# LED_POV_RGB.net
KiCad netlist of a schematic drawn in EAGLE
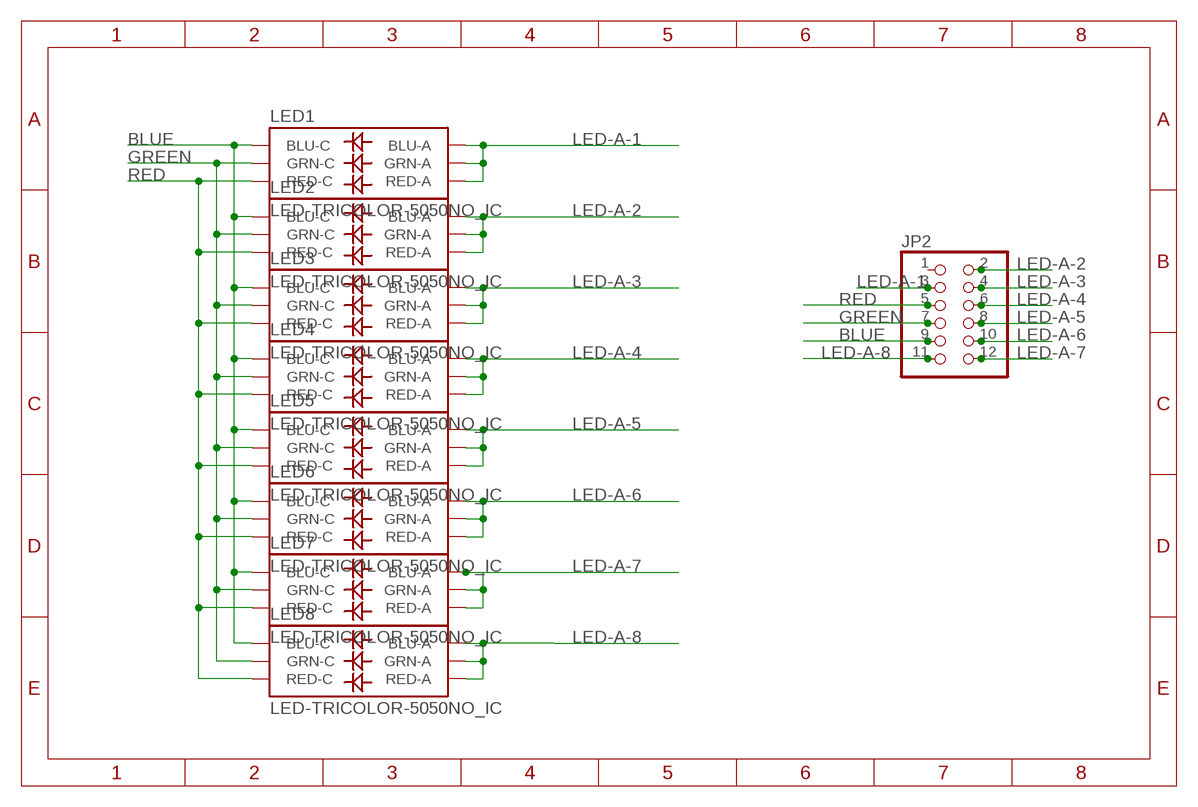
[diagram p0: schematic, sheet 1]

(export (version "E")
  (design (tool "Eeschema 10.0.6"))
  (components
    (comp (ref "JP2")
      (value "PINHD-2X6")
      (footprint "eagle-import:2X06")
      (libsource (lib "eagle-import") (part "PINHD-2X6"))
    )
    (comp (ref "LED1")
      (value "LED-TRICOLOR-5050NO_IC")
      (footprint "eagle-import:LED-TRICOLOR-5050")
      (libsource (lib "eagle-import") (part "LED-TRICOLOR-5050NO_IC"))
    )
    (comp (ref "LED2")
      (value "LED-TRICOLOR-5050NO_IC")
      (footprint "eagle-import:LED-TRICOLOR-5050")
      (libsource (lib "eagle-import") (part "LED-TRICOLOR-5050NO_IC"))
    )
    (comp (ref "LED3")
      (value "LED-TRICOLOR-5050NO_IC")
      (footprint "eagle-import:LED-TRICOLOR-5050")
      (libsource (lib "eagle-import") (part "LED-TRICOLOR-5050NO_IC"))
    )
    (comp (ref "LED4")
      (value "LED-TRICOLOR-5050NO_IC")
      (footprint "eagle-import:LED-TRICOLOR-5050")
      (libsource (lib "eagle-import") (part "LED-TRICOLOR-5050NO_IC"))
    )
    (comp (ref "LED5")
      (value "LED-TRICOLOR-5050NO_IC")
      (footprint "eagle-import:LED-TRICOLOR-5050")
      (libsource (lib "eagle-import") (part "LED-TRICOLOR-5050NO_IC"))
    )
    (comp (ref "LED6")
      (value "LED-TRICOLOR-5050NO_IC")
      (footprint "eagle-import:LED-TRICOLOR-5050")
      (libsource (lib "eagle-import") (part "LED-TRICOLOR-5050NO_IC"))
    )
    (comp (ref "LED7")
      (value "LED-TRICOLOR-5050NO_IC")
      (footprint "eagle-import:LED-TRICOLOR-5050")
      (libsource (lib "eagle-import") (part "LED-TRICOLOR-5050NO_IC"))
    )
    (comp (ref "LED8")
      (value "LED-TRICOLOR-5050NO_IC")
      (footprint "eagle-import:LED-TRICOLOR-5050")
      (libsource (lib "eagle-import") (part "LED-TRICOLOR-5050NO_IC"))
    )
  )
  (nets
    (net (code "1") (name "/BLUE") (class "Default")
      (node (ref "JP2") (pin "9") (pinfunction "9_9") (pintype "passive"))
      (node (ref "LED1") (pin "4") (pinfunction "BLU-C_4") (pintype "bidirectional"))
      (node (ref "LED2") (pin "4") (pinfunction "BLU-C_4") (pintype "bidirectional"))
      (node (ref "LED3") (pin "4") (pinfunction "BLU-C_4") (pintype "bidirectional"))
      (node (ref "LED4") (pin "4") (pinfunction "BLU-C_4") (pintype "bidirectional"))
      (node (ref "LED5") (pin "4") (pinfunction "BLU-C_4") (pintype "bidirectional"))
      (node (ref "LED6") (pin "4") (pinfunction "BLU-C_4") (pintype "bidirectional"))
      (node (ref "LED7") (pin "4") (pinfunction "BLU-C_4") (pintype "bidirectional"))
      (node (ref "LED8") (pin "4") (pinfunction "BLU-C_4") (pintype "bidirectional"))
    )
    (net (code "2") (name "/GREEN") (class "Default")
      (node (ref "JP2") (pin "7") (pinfunction "7_7") (pintype "passive"))
      (node (ref "LED1") (pin "6") (pinfunction "GRN-C_6") (pintype "bidirectional"))
      (node (ref "LED2") (pin "6") (pinfunction "GRN-C_6") (pintype "bidirectional"))
      (node (ref "LED3") (pin "6") (pinfunction "GRN-C_6") (pintype "bidirectional"))
      (node (ref "LED4") (pin "6") (pinfunction "GRN-C_6") (pintype "bidirectional"))
      (node (ref "LED5") (pin "6") (pinfunction "GRN-C_6") (pintype "bidirectional"))
      (node (ref "LED6") (pin "6") (pinfunction "GRN-C_6") (pintype "bidirectional"))
      (node (ref "LED7") (pin "6") (pinfunction "GRN-C_6") (pintype "bidirectional"))
      (node (ref "LED8") (pin "6") (pinfunction "GRN-C_6") (pintype "bidirectional"))
    )
    (net (code "3") (name "/LED-A-1") (class "Default")
      (node (ref "JP2") (pin "3") (pinfunction "3_3") (pintype "passive"))
      (node (ref "LED1") (pin "1") (pinfunction "GRN-A_1") (pintype "bidirectional"))
      (node (ref "LED1") (pin "2") (pinfunction "RED-A_2") (pintype "bidirectional"))
      (node (ref "LED1") (pin "3") (pinfunction "BLU-A_3") (pintype "bidirectional"))
    )
    (net (code "4") (name "/LED-A-2") (class "Default")
      (node (ref "JP2") (pin "2") (pinfunction "2_2") (pintype "passive"))
      (node (ref "LED2") (pin "1") (pinfunction "GRN-A_1") (pintype "bidirectional"))
      (node (ref "LED2") (pin "2") (pinfunction "RED-A_2") (pintype "bidirectional"))
      (node (ref "LED2") (pin "3") (pinfunction "BLU-A_3") (pintype "bidirectional"))
    )
    (net (code "5") (name "/LED-A-3") (class "Default")
      (node (ref "JP2") (pin "4") (pinfunction "4_4") (pintype "passive"))
      (node (ref "LED3") (pin "1") (pinfunction "GRN-A_1") (pintype "bidirectional"))
      (node (ref "LED3") (pin "2") (pinfunction "RED-A_2") (pintype "bidirectional"))
      (node (ref "LED3") (pin "3") (pinfunction "BLU-A_3") (pintype "bidirectional"))
    )
    (net (code "6") (name "/LED-A-4") (class "Default")
      (node (ref "JP2") (pin "6") (pinfunction "6_6") (pintype "passive"))
      (node (ref "LED4") (pin "1") (pinfunction "GRN-A_1") (pintype "bidirectional"))
      (node (ref "LED4") (pin "2") (pinfunction "RED-A_2") (pintype "bidirectional"))
      (node (ref "LED4") (pin "3") (pinfunction "BLU-A_3") (pintype "bidirectional"))
    )
    (net (code "7") (name "/LED-A-5") (class "Default")
      (node (ref "JP2") (pin "8") (pinfunction "8_8") (pintype "passive"))
      (node (ref "LED5") (pin "1") (pinfunction "GRN-A_1") (pintype "bidirectional"))
      (node (ref "LED5") (pin "2") (pinfunction "RED-A_2") (pintype "bidirectional"))
      (node (ref "LED5") (pin "3") (pinfunction "BLU-A_3") (pintype "bidirectional"))
    )
    (net (code "8") (name "/LED-A-6") (class "Default")
      (node (ref "JP2") (pin "10") (pinfunction "10_10") (pintype "passive"))
      (node (ref "LED6") (pin "1") (pinfunction "GRN-A_1") (pintype "bidirectional"))
      (node (ref "LED6") (pin "2") (pinfunction "RED-A_2") (pintype "bidirectional"))
      (node (ref "LED6") (pin "3") (pinfunction "BLU-A_3") (pintype "bidirectional"))
    )
    (net (code "9") (name "/LED-A-7") (class "Default")
      (node (ref "JP2") (pin "12") (pinfunction "12_12") (pintype "passive"))
      (node (ref "LED7") (pin "1") (pinfunction "GRN-A_1") (pintype "bidirectional"))
      (node (ref "LED7") (pin "2") (pinfunction "RED-A_2") (pintype "bidirectional"))
      (node (ref "LED7") (pin "3") (pinfunction "BLU-A_3") (pintype "bidirectional"))
    )
    (net (code "10") (name "/LED-A-8") (class "Default")
      (node (ref "JP2") (pin "11") (pinfunction "11_11") (pintype "passive"))
      (node (ref "LED8") (pin "1") (pinfunction "GRN-A_1") (pintype "bidirectional"))
      (node (ref "LED8") (pin "2") (pinfunction "RED-A_2") (pintype "bidirectional"))
      (node (ref "LED8") (pin "3") (pinfunction "BLU-A_3") (pintype "bidirectional"))
    )
    (net (code "11") (name "/RED") (class "Default")
      (node (ref "JP2") (pin "5") (pinfunction "5_5") (pintype "passive"))
      (node (ref "LED1") (pin "5") (pinfunction "RED-C_5") (pintype "bidirectional"))
      (node (ref "LED2") (pin "5") (pinfunction "RED-C_5") (pintype "bidirectional"))
      (node (ref "LED3") (pin "5") (pinfunction "RED-C_5") (pintype "bidirectional"))
      (node (ref "LED4") (pin "5") (pinfunction "RED-C_5") (pintype "bidirectional"))
      (node (ref "LED5") (pin "5") (pinfunction "RED-C_5") (pintype "bidirectional"))
      (node (ref "LED6") (pin "5") (pinfunction "RED-C_5") (pintype "bidirectional"))
      (node (ref "LED7") (pin "5") (pinfunction "RED-C_5") (pintype "bidirectional"))
      (node (ref "LED8") (pin "5") (pinfunction "RED-C_5") (pintype "bidirectional"))
    )
    (net (code "12") (name "unconnected-(JP2-Pad1)") (class "Default")
      (node (ref "JP2") (pin "1") (pinfunction "1_1") (pintype "passive"))
    )
  )
)
